# CH32FVx0xR-NFC-EVT-R0-1v2.net
KiCad netlist of a schematic drawn in Altium Designer
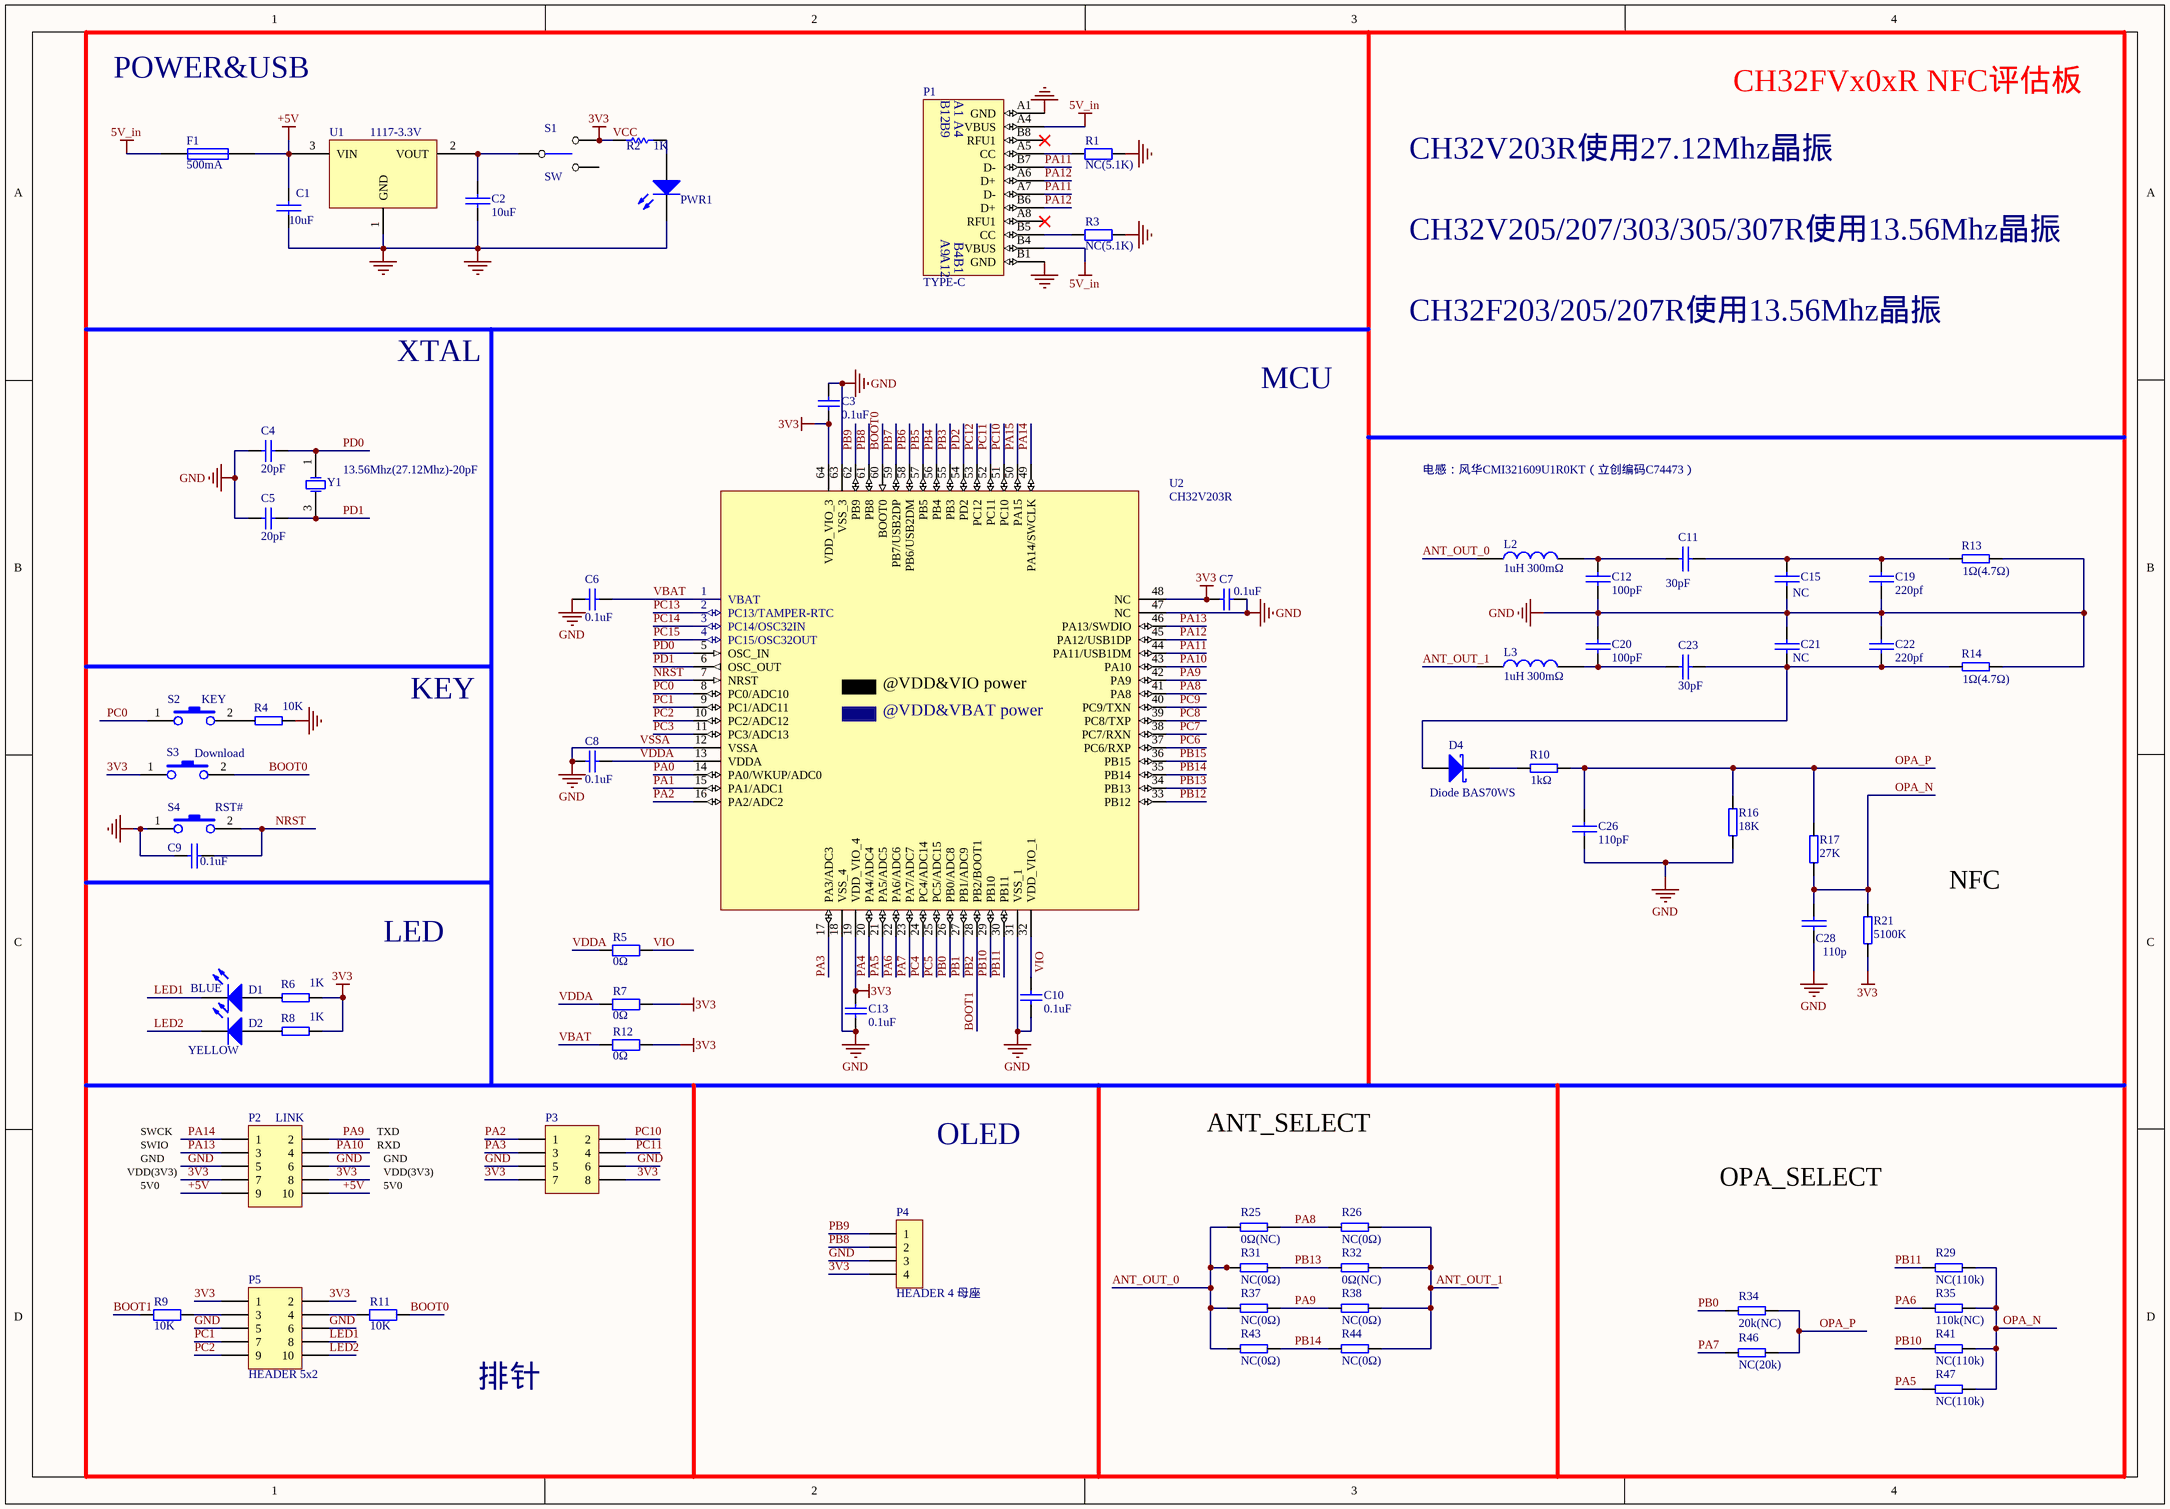
[diagram p0: CH32FVx0xR-NFC-EVT-R0-1v2.SchDoc]

(export (version "E")
  (design (tool "Eeschema 10.0.6"))
  (components
    (comp (ref "C1")
      (value "10uF")
      (footprint "3216_C")
      (description "Capacitor")
      (libsource (lib "") (part "CAP_1"))
    )
    (comp (ref "C2")
      (value "10uF")
      (footprint "3216_C")
      (description "Capacitor")
      (libsource (lib "") (part "CAP_1"))
    )
    (comp (ref "C3")
      (value "0.1uF")
      (footprint "0603_C")
      (description "Capacitor")
      (libsource (lib "Miscellaneous Devices") (part "Cap"))
    )
    (comp (ref "C4")
      (value "20pF")
      (footprint "0603_C")
      (description "Capacitor")
      (libsource (lib "Miscellaneous Devices") (part "Cap"))
    )
    (comp (ref "C5")
      (value "20pF")
      (footprint "0603_C")
      (description "Capacitor")
      (libsource (lib "Miscellaneous Devices") (part "Cap"))
    )
    (comp (ref "C6")
      (value "0.1uF")
      (footprint "0603_C")
      (description "Capacitor")
      (libsource (lib "Miscellaneous Devices") (part "Cap"))
    )
    (comp (ref "C7")
      (value "0.1uF")
      (footprint "0603_C")
      (description "Capacitor")
      (libsource (lib "Miscellaneous Devices") (part "Cap"))
    )
    (comp (ref "C8")
      (value "0.1uF")
      (footprint "0603_C")
      (description "Capacitor")
      (libsource (lib "Miscellaneous Devices") (part "Cap"))
    )
    (comp (ref "C9")
      (value "0.1uF")
      (footprint "0603_C")
      (description "Capacitor")
      (libsource (lib "*") (part "CAP"))
    )
    (comp (ref "C10")
      (value "0.1uF")
      (footprint "0603_C")
      (description "Capacitor")
      (libsource (lib "Miscellaneous Devices") (part "Cap"))
    )
    (comp (ref "C11")
      (value "30pF")
      (footprint "0603_C")
      (description "Capacitor")
      (libsource (lib "wch_sch_others") (part "CAP"))
    )
    (comp (ref "C12")
      (value "100pF")
      (footprint "0603_C")
      (description "Capacitor")
      (libsource (lib "wch_sch_others") (part "CAP"))
    )
    (comp (ref "C13")
      (value "0.1uF")
      (footprint "0603_C")
      (description "Capacitor")
      (libsource (lib "Miscellaneous Devices") (part "Cap"))
    )
    (comp (ref "C15")
      (value "NC")
      (footprint "0603_C")
      (description "Capacitor")
      (libsource (lib "wch_sch_others") (part "CAP"))
    )
    (comp (ref "C19")
      (value "220pf")
      (footprint "0603_C")
      (description "Capacitor")
      (libsource (lib "wch_sch_others") (part "CAP"))
    )
    (comp (ref "C20")
      (value "100pF")
      (footprint "0603_C")
      (description "Capacitor")
      (libsource (lib "wch_sch_others") (part "CAP"))
    )
    (comp (ref "C21")
      (value "NC")
      (footprint "0603_C")
      (description "Capacitor")
      (libsource (lib "wch_sch_others") (part "CAP"))
    )
    (comp (ref "C22")
      (value "220pf")
      (footprint "0603_C")
      (description "Capacitor")
      (libsource (lib "wch_sch_others") (part "CAP"))
    )
    (comp (ref "C23")
      (value "30pF")
      (footprint "0603_C")
      (description "Capacitor")
      (libsource (lib "wch_sch_others") (part "CAP"))
    )
    (comp (ref "C26")
      (value "110pF")
      (footprint "0603_C")
      (description "Capacitor")
      (libsource (lib "wch_sch_others") (part "CAP"))
    )
    (comp (ref "C28")
      (value "110p")
      (footprint "0603_C")
      (description "Capacitor")
      (libsource (lib "wch_sch_others") (part "CAP"))
    )
    (comp (ref "D1")
      (value "BLUE")
      (footprint "0603+")
      (description "Typical INFRARED GaAs LED")
      (fields (field (name "PUBLISHER") "Altium Limited"))
      (libsource (lib "*") (part "LED0"))
    )
    (comp (ref "D2")
      (value "YELLOW")
      (footprint "0603+")
      (description "Typical INFRARED GaAs LED")
      (fields (field (name "PUBLISHER") "Altium Limited"))
      (libsource (lib "*") (part "LED0"))
    )
    (comp (ref "D4")
      (value "Diode BAS70WS")
      (footprint "3528+")
      (description "Silicon AF Schottky Diode for High-Speed Switching")
      (fields (field (name "PUBLISHER") "Altium Limited"))
      (libsource (lib "Miscellaneous Devices") (part "Diode BAS70"))
    )
    (comp (ref "F1")
      (value "500mA")
      (footprint "0805")
      (description "Fuse")
      (libsource (lib "*") (part "FUSE1"))
    )
    (comp (ref "L2") (value "1uH 300mΩ") (footprint "0805") (libsource (lib "*") (part "INDUCTOR")))
    (comp (ref "L3") (value "1uH 300mΩ") (footprint "0805") (libsource (lib "*") (part "INDUCTOR")))
    (comp (ref "P1")
      (value "TYPE-C")
      (footprint "TYPE-C-Receptacle-2.0")
      (libsource (lib "*") (part "TYPE-C1"))
    )
    (comp (ref "P2")
      (value "LINK")
      (footprint "IDC10-2.54mm")
      (description "Header, 5-Pin, Dual row, Right Angle")
      (fields (field (name "PUBLISHER") "Altium Limited"))
      (libsource (lib "Miscellaneous Connectors") (part "Header 5X2H"))
    )
    (comp (ref "P3")
      (value "Header 4X2")
      (footprint "IDC8-2.54mm")
      (description "Header, 4-Pin, Dual row")
      (fields (field (name "PUBLISHER") "Altium Limited"))
      (libsource (lib "Miscellaneous Connectors") (part "Header 4X2"))
    )
    (comp (ref "P4")
      (value "HEADER 4 母座")
      (footprint "SIP4-2.54mm")
      (description "Header, 4-Pin")
      (libsource (lib "wch_sch_others") (part "HEADER 4"))
    )
    (comp (ref "P5")
      (value "HEADER 5x2")
      (footprint "MYPCB:IDC10-2.54mm")
      (description "Header, 5-Pin, Dual row")
      (libsource (lib "wch_sch_others") (part "HEADER 5x2"))
    )
    (comp (ref "PWR1")
      (value "POWER  red")
      (footprint "0603+")
      (description "Typical INFRARED GaAs LED")
      (fields (field (name "PUBLISHER") "Altium Limited"))
      (libsource (lib "Miscellaneous Devices") (part "LED0"))
    )
    (comp (ref "R1")
      (value "NC(5.1K)")
      (footprint "0603")
      (description "Resistor")
      (libsource (lib "") (part "Res2_1"))
    )
    (comp (ref "R2")
      (value "1K")
      (footprint "0603")
      (description "Semiconductor Resistor")
      (libsource (lib "Miscellaneous Devices") (part "Res Semi"))
    )
    (comp (ref "R3")
      (value "NC(5.1K)")
      (footprint "0603")
      (description "Resistor")
      (libsource (lib "") (part "Res2_1"))
    )
    (comp (ref "R4") (value "10K") (footprint "0603") (libsource (lib "wch_sch_others") (part "RES")))
    (comp (ref "R5")
      (value "0Ω")
      (footprint "0603")
      (description "Resistor")
      (libsource (lib "Miscellaneous Devices") (part "Res2"))
    )
    (comp (ref "R6") (value "1K") (footprint "0603") (libsource (lib "wch_sch_others") (part "RES")))
    (comp (ref "R7")
      (value "0Ω")
      (footprint "0603")
      (description "Resistor")
      (libsource (lib "Miscellaneous Devices") (part "Res2"))
    )
    (comp (ref "R8") (value "1K") (footprint "0603") (libsource (lib "wch_sch_others") (part "RES")))
    (comp (ref "R9")
      (value "10K")
      (footprint "0603")
      (description "Resistor")
      (libsource (lib "") (part "Res2_1"))
    )
    (comp (ref "R10") (value "1kΩ") (footprint "0603") (libsource (lib "wch_sch_others") (part "RES")))
    (comp (ref "R11")
      (value "10K")
      (footprint "0603")
      (description "Resistor")
      (libsource (lib "") (part "Res2_1"))
    )
    (comp (ref "R12")
      (value "0Ω")
      (footprint "0603")
      (description "Resistor")
      (libsource (lib "Miscellaneous Devices") (part "Res2"))
    )
    (comp (ref "R13") (value "1Ω(4.7Ω)") (footprint "0603") (libsource (lib "wch_sch_others") (part "RES")))
    (comp (ref "R14") (value "1Ω(4.7Ω)") (footprint "0603") (libsource (lib "wch_sch_others") (part "RES")))
    (comp (ref "R16") (value "18K") (footprint "0603") (libsource (lib "wch_sch_others") (part "RES")))
    (comp (ref "R17") (value "27K") (footprint "0603") (libsource (lib "wch_sch_others") (part "RES")))
    (comp (ref "R21") (value "5100K") (footprint "0603") (libsource (lib "wch_sch_others") (part "RES")))
    (comp (ref "R25") (value "0Ω(NC)") (footprint "0603") (libsource (lib "wch_sch_others") (part "RES")))
    (comp (ref "R26") (value "NC(0Ω)") (footprint "0603") (libsource (lib "wch_sch_others") (part "RES")))
    (comp (ref "R29") (value "NC(110k)") (footprint "0603") (libsource (lib "wch_sch_others") (part "RES")))
    (comp (ref "R31") (value "NC(0Ω)") (footprint "0603") (libsource (lib "wch_sch_others") (part "RES")))
    (comp (ref "R32") (value "0Ω(NC)") (footprint "0603") (libsource (lib "wch_sch_others") (part "RES")))
    (comp (ref "R34") (value "20k(NC)") (footprint "0603") (libsource (lib "wch_sch_others") (part "RES")))
    (comp (ref "R35") (value "110k(NC)") (footprint "0603") (libsource (lib "wch_sch_others") (part "RES")))
    (comp (ref "R37") (value "NC(0Ω)") (footprint "0603") (libsource (lib "wch_sch_others") (part "RES")))
    (comp (ref "R38") (value "NC(0Ω)") (footprint "0603") (libsource (lib "wch_sch_others") (part "RES")))
    (comp (ref "R41") (value "NC(110k)") (footprint "0603") (libsource (lib "wch_sch_others") (part "RES")))
    (comp (ref "R43") (value "NC(0Ω)") (footprint "0603") (libsource (lib "wch_sch_others") (part "RES")))
    (comp (ref "R44") (value "NC(0Ω)") (footprint "0603") (libsource (lib "wch_sch_others") (part "RES")))
    (comp (ref "R46") (value "NC(20k)") (footprint "0603") (libsource (lib "wch_sch_others") (part "RES")))
    (comp (ref "R47") (value "NC(110k)") (footprint "0603") (libsource (lib "wch_sch_others") (part "RES")))
    (comp (ref "S1") (value "SW") (footprint "SW1") (libsource (lib "MYSCH") (part "SW")))
    (comp (ref "S2")
      (value "KEY")
      (footprint "SMD_6.1x3.65x2.5mm-KEY")
      (libsource (lib "wch_sch_others") (part "KEY1"))
    )
    (comp (ref "S3")
      (value "Download")
      (footprint "SMD_6.1x3.65x2.5mm-KEY")
      (libsource (lib "wch_sch_others") (part "KEY1"))
    )
    (comp (ref "S4")
      (value "RST#")
      (footprint "SMD_6.1x3.65x2.5mm-KEY")
      (libsource (lib "wch_sch_others") (part "KEY1"))
    )
    (comp (ref "U1")
      (value "1117-3.3V")
      (footprint "SOT-223")
      (libsource (lib "wch_sch_others") (part "1117-3.3V"))
    )
    (comp (ref "U2")
      (value "CH32V203R")
      (footprint "LQFP64M_10x10")
      (description "RISC-V HD-MCU, 10M Ethernet, 2*USB, CAN")
      (libsource (lib "CHXXX") (part "CH32V203R"))
    )
    (comp (ref "Y1")
      (value "13.56Mhz(27.12Mhz)-20pF")
      (footprint "XT3225")
      (description "Crystal Oscillator")
      (fields (field (name "PUBLISHER") "Altium Limited"))
      (libsource (lib "Miscellaneous Devices") (part "XTAL"))
    )
  )
  (nets
    (net (code "1") (name "+5V") (class "Default")
      (node (ref "C1") (pin "1") (pinfunction "1_1") (pintype "passive"))
      (node (ref "F1") (pin "2") (pinfunction "2_2") (pintype "passive"))
      (node (ref "P2") (pin "10") (pinfunction "10_10") (pintype "passive"))
      (node (ref "P2") (pin "9") (pinfunction "9_9") (pintype "passive"))
      (node (ref "U1") (pin "3") (pinfunction "VIN_3") (pintype "passive"))
    )
    (net (code "2") (name "/ANT_OUT_0") (class "Default")
      (node (ref "L2") (pin "1") (pinfunction "1_1") (pintype "passive"))
      (node (ref "R25") (pin "2") (pintype "passive"))
      (node (ref "R31") (pin "2") (pintype "passive"))
      (node (ref "R37") (pin "2") (pintype "passive"))
      (node (ref "R43") (pin "2") (pintype "passive"))
    )
    (net (code "3") (name "/ANT_OUT_1") (class "Default")
      (node (ref "L3") (pin "1") (pinfunction "1_1") (pintype "passive"))
      (node (ref "R26") (pin "1") (pintype "passive"))
      (node (ref "R32") (pin "1") (pintype "passive"))
      (node (ref "R38") (pin "1") (pintype "passive"))
      (node (ref "R44") (pin "1") (pintype "passive"))
    )
    (net (code "4") (name "/BOOT0") (class "Default")
      (node (ref "R11") (pin "2") (pinfunction "2_2") (pintype "passive"))
      (node (ref "S3") (pin "2") (pinfunction "2_2") (pintype "passive"))
      (node (ref "U2") (pin "60") (pinfunction "BOOT0_60") (pintype "input"))
    )
    (net (code "5") (name "/BOOT1") (class "Default")
      (node (ref "R9") (pin "1") (pinfunction "1_1") (pintype "passive"))
      (node (ref "U2") (pin "28") (pinfunction "PB2/BOOT1_28") (pintype "bidirectional"))
    )
    (net (code "6") (name "/LED1") (class "Default")
      (node (ref "D1") (pin "2") (pinfunction "K_2") (pintype "passive"))
      (node (ref "P5") (pin "8") (pinfunction "8_8") (pintype "passive"))
    )
    (net (code "7") (name "/LED2") (class "Default")
      (node (ref "D2") (pin "2") (pinfunction "K_2") (pintype "passive"))
      (node (ref "P5") (pin "10") (pinfunction "10_10") (pintype "passive"))
    )
    (net (code "8") (name "/NRST") (class "Default")
      (node (ref "C9") (pin "2") (pinfunction "2_2") (pintype "passive"))
      (node (ref "S4") (pin "2") (pinfunction "2_2") (pintype "passive"))
      (node (ref "U2") (pin "7") (pinfunction "NRST_7") (pintype "input"))
    )
    (net (code "9") (name "/OPA_N") (class "Default")
      (node (ref "C28") (pin "2") (pinfunction "2_2") (pintype "passive"))
      (node (ref "R17") (pin "1") (pintype "passive"))
      (node (ref "R21") (pin "2") (pintype "passive"))
      (node (ref "R29") (pin "1") (pintype "passive"))
      (node (ref "R35") (pin "1") (pintype "passive"))
      (node (ref "R41") (pin "1") (pintype "passive"))
      (node (ref "R47") (pin "1") (pintype "passive"))
    )
    (net (code "10") (name "/OPA_P") (class "Default")
      (node (ref "C26") (pin "2") (pinfunction "2_2") (pintype "passive"))
      (node (ref "R10") (pin "2") (pintype "passive"))
      (node (ref "R16") (pin "2") (pintype "passive"))
      (node (ref "R17") (pin "2") (pintype "passive"))
      (node (ref "R34") (pin "1") (pintype "passive"))
      (node (ref "R46") (pin "1") (pintype "passive"))
    )
    (net (code "11") (name "/PA0") (class "Default")
      (node (ref "U2") (pin "14") (pinfunction "PA0/WKUP/ADC0_14") (pintype "bidirectional"))
    )
    (net (code "12") (name "/PA1") (class "Default")
      (node (ref "U2") (pin "15") (pinfunction "PA1/ADC1_15") (pintype "bidirectional"))
    )
    (net (code "13") (name "/PA2") (class "Default")
      (node (ref "P3") (pin "1") (pinfunction "1_1") (pintype "passive"))
      (node (ref "U2") (pin "16") (pinfunction "PA2/ADC2_16") (pintype "bidirectional"))
    )
    (net (code "14") (name "/PA3") (class "Default")
      (node (ref "P3") (pin "3") (pinfunction "3_3") (pintype "passive"))
      (node (ref "U2") (pin "17") (pinfunction "PA3/ADC3_17") (pintype "bidirectional"))
    )
    (net (code "15") (name "/PA4") (class "Default")
      (node (ref "U2") (pin "20") (pinfunction "PA4/ADC4_20") (pintype "bidirectional"))
    )
    (net (code "16") (name "/PA5") (class "Default")
      (node (ref "R47") (pin "2") (pintype "passive"))
      (node (ref "U2") (pin "21") (pinfunction "PA5/ADC5_21") (pintype "bidirectional"))
    )
    (net (code "17") (name "/PA6") (class "Default")
      (node (ref "R35") (pin "2") (pintype "passive"))
      (node (ref "U2") (pin "22") (pinfunction "PA6/ADC6_22") (pintype "bidirectional"))
    )
    (net (code "18") (name "/PA7") (class "Default")
      (node (ref "R46") (pin "2") (pintype "passive"))
      (node (ref "U2") (pin "23") (pinfunction "PA7/ADC7_23") (pintype "bidirectional"))
    )
    (net (code "19") (name "/PA8") (class "Default")
      (node (ref "R25") (pin "1") (pintype "passive"))
      (node (ref "R26") (pin "2") (pintype "passive"))
      (node (ref "U2") (pin "41") (pinfunction "PA8_41") (pintype "bidirectional"))
    )
    (net (code "20") (name "/PA9") (class "Default")
      (node (ref "P2") (pin "2") (pinfunction "2_2") (pintype "passive"))
      (node (ref "R37") (pin "1") (pintype "passive"))
      (node (ref "R38") (pin "2") (pintype "passive"))
      (node (ref "U2") (pin "42") (pinfunction "PA9_42") (pintype "bidirectional"))
    )
    (net (code "21") (name "/PA10") (class "Default")
      (node (ref "P2") (pin "4") (pinfunction "4_4") (pintype "passive"))
      (node (ref "U2") (pin "43") (pinfunction "PA10_43") (pintype "bidirectional"))
    )
    (net (code "22") (name "/PA11") (class "Default")
      (node (ref "P1") (pin "A7") (pinfunction "D-_A7") (pintype "bidirectional"))
      (node (ref "P1") (pin "B7") (pinfunction "D-_B7") (pintype "bidirectional"))
      (node (ref "U2") (pin "44") (pinfunction "PA11/USB1DM_44") (pintype "bidirectional"))
    )
    (net (code "23") (name "/PA12") (class "Default")
      (node (ref "P1") (pin "A6") (pinfunction "D+_A6") (pintype "bidirectional"))
      (node (ref "P1") (pin "B6") (pinfunction "D+_B6") (pintype "bidirectional"))
      (node (ref "U2") (pin "45") (pinfunction "PA12/USB1DP_45") (pintype "bidirectional"))
    )
    (net (code "24") (name "/PA13") (class "Default")
      (node (ref "P2") (pin "3") (pinfunction "3_3") (pintype "passive"))
      (node (ref "U2") (pin "46") (pinfunction "PA13/SWDIO_46") (pintype "bidirectional"))
    )
    (net (code "25") (name "/PA14") (class "Default")
      (node (ref "P2") (pin "1") (pinfunction "1_1") (pintype "passive"))
      (node (ref "U2") (pin "49") (pinfunction "PA14/SWCLK_49") (pintype "bidirectional"))
    )
    (net (code "26") (name "/PA15") (class "Default")
      (node (ref "U2") (pin "50") (pinfunction "PA15_50") (pintype "bidirectional"))
    )
    (net (code "27") (name "/PB0") (class "Default")
      (node (ref "R34") (pin "2") (pintype "passive"))
      (node (ref "U2") (pin "26") (pinfunction "PB0/ADC8_26") (pintype "bidirectional"))
    )
    (net (code "28") (name "/PB1") (class "Default")
      (node (ref "U2") (pin "27") (pinfunction "PB1/ADC9_27") (pintype "bidirectional"))
    )
    (net (code "29") (name "/PB3") (class "Default")
      (node (ref "U2") (pin "55") (pinfunction "PB3_55") (pintype "bidirectional"))
    )
    (net (code "30") (name "/PB4") (class "Default")
      (node (ref "U2") (pin "56") (pinfunction "PB4_56") (pintype "bidirectional"))
    )
    (net (code "31") (name "/PB5") (class "Default")
      (node (ref "U2") (pin "57") (pinfunction "PB5_57") (pintype "bidirectional"))
    )
    (net (code "32") (name "/PB6") (class "Default")
      (node (ref "U2") (pin "58") (pinfunction "PB6/USB2DM_58") (pintype "bidirectional"))
    )
    (net (code "33") (name "/PB7") (class "Default")
      (node (ref "U2") (pin "59") (pinfunction "PB7/USB2DP_59") (pintype "bidirectional"))
    )
    (net (code "34") (name "/PB8") (class "Default")
      (node (ref "P4") (pin "2") (pinfunction "2_2") (pintype "passive"))
      (node (ref "U2") (pin "61") (pinfunction "PB8_61") (pintype "bidirectional"))
    )
    (net (code "35") (name "/PB9") (class "Default")
      (node (ref "P4") (pin "1") (pinfunction "1_1") (pintype "passive"))
      (node (ref "U2") (pin "62") (pinfunction "PB9_62") (pintype "bidirectional"))
    )
    (net (code "36") (name "/PB10") (class "Default")
      (node (ref "R41") (pin "2") (pintype "passive"))
      (node (ref "U2") (pin "29") (pinfunction "PB10_29") (pintype "bidirectional"))
    )
    (net (code "37") (name "/PB11") (class "Default")
      (node (ref "R29") (pin "2") (pintype "passive"))
      (node (ref "U2") (pin "30") (pinfunction "PB11_30") (pintype "bidirectional"))
    )
    (net (code "38") (name "/PB12") (class "Default")
      (node (ref "U2") (pin "33") (pinfunction "PB12_33") (pintype "bidirectional"))
    )
    (net (code "39") (name "/PB13") (class "Default")
      (node (ref "R31") (pin "1") (pintype "passive"))
      (node (ref "R32") (pin "2") (pintype "passive"))
      (node (ref "U2") (pin "34") (pinfunction "PB13_34") (pintype "bidirectional"))
    )
    (net (code "40") (name "/PB14") (class "Default")
      (node (ref "R43") (pin "1") (pintype "passive"))
      (node (ref "R44") (pin "2") (pintype "passive"))
      (node (ref "U2") (pin "35") (pinfunction "PB14_35") (pintype "bidirectional"))
    )
    (net (code "41") (name "/PB15") (class "Default")
      (node (ref "U2") (pin "36") (pinfunction "PB15_36") (pintype "bidirectional"))
    )
    (net (code "42") (name "/PC0") (class "Default")
      (node (ref "S2") (pin "1") (pinfunction "1_1") (pintype "passive"))
      (node (ref "U2") (pin "8") (pinfunction "PC0/ADC10_8") (pintype "bidirectional"))
    )
    (net (code "43") (name "/PC1") (class "Default")
      (node (ref "P5") (pin "7") (pinfunction "7_7") (pintype "passive"))
      (node (ref "U2") (pin "9") (pinfunction "PC1/ADC11_9") (pintype "bidirectional"))
    )
    (net (code "44") (name "/PC2") (class "Default")
      (node (ref "P5") (pin "9") (pinfunction "9_9") (pintype "passive"))
      (node (ref "U2") (pin "10") (pinfunction "PC2/ADC12_10") (pintype "bidirectional"))
    )
    (net (code "45") (name "/PC3") (class "Default")
      (node (ref "U2") (pin "11") (pinfunction "PC3/ADC13_11") (pintype "bidirectional"))
    )
    (net (code "46") (name "/PC4") (class "Default")
      (node (ref "U2") (pin "24") (pinfunction "PC4/ADC14_24") (pintype "bidirectional"))
    )
    (net (code "47") (name "/PC5") (class "Default")
      (node (ref "U2") (pin "25") (pinfunction "PC5/ADC15_25") (pintype "bidirectional"))
    )
    (net (code "48") (name "/PC6") (class "Default")
      (node (ref "U2") (pin "37") (pinfunction "PC6/RXP_37") (pintype "bidirectional"))
    )
    (net (code "49") (name "/PC7") (class "Default")
      (node (ref "U2") (pin "38") (pinfunction "PC7/RXN_38") (pintype "bidirectional"))
    )
    (net (code "50") (name "/PC8") (class "Default")
      (node (ref "U2") (pin "39") (pinfunction "PC8/TXP_39") (pintype "bidirectional"))
    )
    (net (code "51") (name "/PC9") (class "Default")
      (node (ref "U2") (pin "40") (pinfunction "PC9/TXN_40") (pintype "bidirectional"))
    )
    (net (code "52") (name "/PC10") (class "Default")
      (node (ref "P3") (pin "2") (pinfunction "2_2") (pintype "passive"))
      (node (ref "U2") (pin "51") (pinfunction "PC10_51") (pintype "bidirectional"))
    )
    (net (code "53") (name "/PC11") (class "Default")
      (node (ref "P3") (pin "4") (pinfunction "4_4") (pintype "passive"))
      (node (ref "U2") (pin "52") (pinfunction "PC11_52") (pintype "bidirectional"))
    )
    (net (code "54") (name "/PC12") (class "Default")
      (node (ref "U2") (pin "53") (pinfunction "PC12_53") (pintype "bidirectional"))
    )
    (net (code "55") (name "/PC13") (class "Default")
      (node (ref "U2") (pin "2") (pinfunction "PC13/TAMPER-RTC_2") (pintype "bidirectional"))
    )
    (net (code "56") (name "/PC14") (class "Default")
      (node (ref "U2") (pin "3") (pinfunction "PC14/OSC32IN_3") (pintype "bidirectional"))
    )
    (net (code "57") (name "/PC15") (class "Default")
      (node (ref "U2") (pin "4") (pinfunction "PC15/OSC32OUT_4") (pintype "bidirectional"))
    )
    (net (code "58") (name "/PD0") (class "Default")
      (node (ref "C4") (pin "2") (pinfunction "2_2") (pintype "passive"))
      (node (ref "U2") (pin "5") (pinfunction "OSC_IN_5") (pintype "input"))
      (node (ref "Y1") (pin "1") (pinfunction "OSC1_1") (pintype "passive"))
    )
    (net (code "59") (name "/PD1") (class "Default")
      (node (ref "C5") (pin "2") (pinfunction "2_2") (pintype "passive"))
      (node (ref "U2") (pin "6") (pinfunction "OSC_OUT_6") (pintype "output"))
      (node (ref "Y1") (pin "3") (pinfunction "OSC2_3") (pintype "passive"))
    )
    (net (code "60") (name "/PD2") (class "Default")
      (node (ref "U2") (pin "54") (pinfunction "PD2_54") (pintype "bidirectional"))
    )
    (net (code "61") (name "/VBAT") (class "Default")
      (node (ref "C6") (pin "1") (pinfunction "1_1") (pintype "passive"))
      (node (ref "R12") (pin "2") (pinfunction "2_2") (pintype "passive"))
      (node (ref "U2") (pin "1") (pinfunction "VBAT_1") (pintype "power_in"))
    )
    (net (code "62") (name "/VDDA") (class "Default")
      (node (ref "C8") (pin "1") (pinfunction "1_1") (pintype "passive"))
      (node (ref "R5") (pin "2") (pinfunction "2_2") (pintype "passive"))
      (node (ref "R7") (pin "2") (pinfunction "2_2") (pintype "passive"))
      (node (ref "U2") (pin "13") (pinfunction "VDDA_13") (pintype "power_in"))
    )
    (net (code "63") (name "/VIO") (class "Default")
      (node (ref "C10") (pin "2") (pinfunction "2_2") (pintype "passive"))
      (node (ref "R5") (pin "1") (pinfunction "1_1") (pintype "passive"))
      (node (ref "U2") (pin "32") (pinfunction "VDD_VIO_1_32") (pintype "power_in"))
    )
    (net (code "64") (name "3V3") (class "Default")
      (node (ref "C13") (pin "2") (pinfunction "2_2") (pintype "passive"))
      (node (ref "C3") (pin "2") (pinfunction "2_2") (pintype "passive"))
      (node (ref "C7") (pin "2") (pinfunction "2_2") (pintype "passive"))
      (node (ref "P2") (pin "7") (pinfunction "7_7") (pintype "passive"))
      (node (ref "P2") (pin "8") (pinfunction "8_8") (pintype "passive"))
      (node (ref "P3") (pin "7") (pinfunction "7_7") (pintype "passive"))
      (node (ref "P3") (pin "8") (pinfunction "8_8") (pintype "passive"))
      (node (ref "P4") (pin "4") (pinfunction "4_4") (pintype "passive"))
      (node (ref "P5") (pin "1") (pinfunction "1_1") (pintype "passive"))
      (node (ref "P5") (pin "2") (pinfunction "2_2") (pintype "passive"))
      (node (ref "R12") (pin "1") (pinfunction "1_1") (pintype "passive"))
      (node (ref "R2") (pin "2") (pinfunction "2_2") (pintype "passive"))
      (node (ref "R21") (pin "1") (pintype "passive"))
      (node (ref "R6") (pin "1") (pintype "passive"))
      (node (ref "R7") (pin "1") (pinfunction "1_1") (pintype "passive"))
      (node (ref "R8") (pin "1") (pintype "passive"))
      (node (ref "S1") (pin "3") (pinfunction "3_3") (pintype "passive"))
      (node (ref "S3") (pin "1") (pinfunction "1_1") (pintype "passive"))
      (node (ref "U2") (pin "19") (pinfunction "VDD_VIO_4_19") (pintype "power_in"))
      (node (ref "U2") (pin "48") (pinfunction "NC_48") (pintype "power_in"))
      (node (ref "U2") (pin "64") (pinfunction "VDD_VIO_3_64") (pintype "power_in"))
    )
    (net (code "65") (name "5V_in") (class "Default")
      (node (ref "F1") (pin "1") (pinfunction "1_1") (pintype "passive"))
      (node (ref "P1") (pin "A4") (pinfunction "VBUS_A4") (pintype "bidirectional"))
      (node (ref "P1") (pin "B4") (pinfunction "VBUS_B4") (pintype "bidirectional"))
    )
    (net (code "66") (name "GND") (class "Default")
      (node (ref "C1") (pin "2") (pinfunction "2_2") (pintype "passive"))
      (node (ref "C10") (pin "1") (pinfunction "1_1") (pintype "passive"))
      (node (ref "C12") (pin "1") (pinfunction "1_1") (pintype "passive"))
      (node (ref "C13") (pin "1") (pinfunction "1_1") (pintype "passive"))
      (node (ref "C15") (pin "1") (pinfunction "1_1") (pintype "passive"))
      (node (ref "C19") (pin "1") (pinfunction "1_1") (pintype "passive"))
      (node (ref "C2") (pin "2") (pinfunction "2_2") (pintype "passive"))
      (node (ref "C20") (pin "2") (pinfunction "2_2") (pintype "passive"))
      (node (ref "C21") (pin "2") (pinfunction "2_2") (pintype "passive"))
      (node (ref "C22") (pin "2") (pinfunction "2_2") (pintype "passive"))
      (node (ref "C26") (pin "1") (pinfunction "1_1") (pintype "passive"))
      (node (ref "C28") (pin "1") (pinfunction "1_1") (pintype "passive"))
      (node (ref "C3") (pin "1") (pinfunction "1_1") (pintype "passive"))
      (node (ref "C4") (pin "1") (pinfunction "1_1") (pintype "passive"))
      (node (ref "C5") (pin "1") (pinfunction "1_1") (pintype "passive"))
      (node (ref "C6") (pin "2") (pinfunction "2_2") (pintype "passive"))
      (node (ref "C7") (pin "1") (pinfunction "1_1") (pintype "passive"))
      (node (ref "C8") (pin "2") (pinfunction "2_2") (pintype "passive"))
      (node (ref "C9") (pin "1") (pinfunction "1_1") (pintype "passive"))
      (node (ref "P1") (pin "A1") (pinfunction "GND_A1") (pintype "bidirectional"))
      (node (ref "P1") (pin "B1") (pinfunction "GND_B1") (pintype "bidirectional"))
      (node (ref "P2") (pin "5") (pinfunction "5_5") (pintype "passive"))
      (node (ref "P2") (pin "6") (pinfunction "6_6") (pintype "passive"))
      (node (ref "P3") (pin "5") (pinfunction "5_5") (pintype "passive"))
      (node (ref "P3") (pin "6") (pinfunction "6_6") (pintype "passive"))
      (node (ref "P4") (pin "3") (pinfunction "3_3") (pintype "passive"))
      (node (ref "P5") (pin "5") (pinfunction "5_5") (pintype "passive"))
      (node (ref "P5") (pin "6") (pinfunction "6_6") (pintype "passive"))
      (node (ref "PWR1") (pin "2") (pinfunction "K_2") (pintype "passive"))
      (node (ref "R1") (pin "2") (pinfunction "2_2") (pintype "passive"))
      (node (ref "R13") (pin "2") (pintype "passive"))
      (node (ref "R14") (pin "2") (pintype "passive"))
      (node (ref "R16") (pin "1") (pintype "passive"))
      (node (ref "R3") (pin "2") (pinfunction "2_2") (pintype "passive"))
      (node (ref "R4") (pin "1") (pintype "passive"))
      (node (ref "S4") (pin "1") (pinfunction "1_1") (pintype "passive"))
      (node (ref "U1") (pin "1") (pinfunction "GND_1") (pintype "passive"))
      (node (ref "U2") (pin "12") (pinfunction "VSSA_12") (pintype "power_in"))
      (node (ref "U2") (pin "18") (pinfunction "VSS_4_18") (pintype "power_in"))
      (node (ref "U2") (pin "31") (pinfunction "VSS_1_31") (pintype "power_in"))
      (node (ref "U2") (pin "47") (pinfunction "NC_47") (pintype "power_in"))
      (node (ref "U2") (pin "63") (pinfunction "VSS_3_63") (pintype "power_in"))
    )
    (net (code "67") (name "Net-(C11-Pad1)") (class "Default")
      (node (ref "C11") (pin "1") (pinfunction "1_1") (pintype "passive"))
      (node (ref "C12") (pin "2") (pinfunction "2_2") (pintype "passive"))
      (node (ref "L2") (pin "2") (pinfunction "2_2") (pintype "passive"))
    )
    (net (code "68") (name "Net-(C11-Pad2)") (class "Default")
      (node (ref "C11") (pin "2") (pinfunction "2_2") (pintype "passive"))
      (node (ref "C15") (pin "2") (pinfunction "2_2") (pintype "passive"))
      (node (ref "C19") (pin "2") (pinfunction "2_2") (pintype "passive"))
      (node (ref "R13") (pin "1") (pintype "passive"))
    )
    (net (code "69") (name "Net-(C20-Pad1)") (class "Default")
      (node (ref "C20") (pin "1") (pinfunction "1_1") (pintype "passive"))
      (node (ref "C23") (pin "1") (pinfunction "1_1") (pintype "passive"))
      (node (ref "L3") (pin "2") (pinfunction "2_2") (pintype "passive"))
    )
    (net (code "70") (name "Net-(D1-A)") (class "Default")
      (node (ref "D1") (pin "1") (pinfunction "A_1") (pintype "passive"))
      (node (ref "R6") (pin "2") (pintype "passive"))
    )
    (net (code "71") (name "Net-(D2-A)") (class "Default")
      (node (ref "D2") (pin "1") (pinfunction "A_1") (pintype "passive"))
      (node (ref "R8") (pin "2") (pintype "passive"))
    )
    (net (code "72") (name "Net-(D4-A)") (class "Default")
      (node (ref "C21") (pin "1") (pinfunction "1_1") (pintype "passive"))
      (node (ref "C22") (pin "1") (pinfunction "1_1") (pintype "passive"))
      (node (ref "C23") (pin "2") (pinfunction "2_2") (pintype "passive"))
      (node (ref "D4") (pin "1") (pinfunction "A_1") (pintype "passive"))
      (node (ref "R14") (pin "1") (pintype "passive"))
    )
    (net (code "73") (name "Net-(D4-K)") (class "Default")
      (node (ref "D4") (pin "2") (pinfunction "K_2") (pintype "passive"))
      (node (ref "R10") (pin "1") (pintype "passive"))
    )
    (net (code "74") (name "Net-(P1-CC-PadA5)") (class "Default")
      (node (ref "P1") (pin "A5") (pinfunction "CC_A5") (pintype "bidirectional"))
      (node (ref "R1") (pin "1") (pinfunction "1_1") (pintype "passive"))
    )
    (net (code "75") (name "Net-(P1-CC-PadB5)") (class "Default")
      (node (ref "P1") (pin "B5") (pinfunction "CC_B5") (pintype "bidirectional"))
      (node (ref "R3") (pin "1") (pinfunction "1_1") (pintype "passive"))
    )
    (net (code "76") (name "Net-(P5-Pad3)") (class "Default")
      (node (ref "P5") (pin "3") (pinfunction "3_3") (pintype "passive"))
      (node (ref "R9") (pin "2") (pinfunction "2_2") (pintype "passive"))
    )
    (net (code "77") (name "Net-(P5-Pad4)") (class "Default")
      (node (ref "P5") (pin "4") (pinfunction "4_4") (pintype "passive"))
      (node (ref "R11") (pin "1") (pinfunction "1_1") (pintype "passive"))
    )
    (net (code "78") (name "Net-(PWR1-A)") (class "Default")
      (node (ref "PWR1") (pin "1") (pinfunction "A_1") (pintype "passive"))
      (node (ref "R2") (pin "1") (pinfunction "1_1") (pintype "passive"))
    )
    (net (code "79") (name "Net-(R4-Pad2)") (class "Default")
      (node (ref "R4") (pin "2") (pintype "passive"))
      (node (ref "S2") (pin "2") (pinfunction "2_2") (pintype "passive"))
    )
    (net (code "80") (name "Net-(U1-VOUT)") (class "Default")
      (node (ref "C2") (pin "1") (pinfunction "1_1") (pintype "passive"))
      (node (ref "S1") (pin "1") (pinfunction "1_1") (pintype "passive"))
      (node (ref "U1") (pin "2") (pinfunction "VOUT_2") (pintype "passive"))
    )
    (net (code "81") (name "unconnected-(P1-RFU1-PadA8)") (class "Default")
      (node (ref "P1") (pin "A8") (pinfunction "RFU1_A8") (pintype "bidirectional+no_connect"))
    )
    (net (code "82") (name "unconnected-(P1-RFU1-PadB8)") (class "Default")
      (node (ref "P1") (pin "B8") (pinfunction "RFU1_B8") (pintype "bidirectional+no_connect"))
    )
    (net (code "83") (name "unconnected-(S1-Pad2)") (class "Default")
      (node (ref "S1") (pin "2") (pinfunction "2_2") (pintype "passive"))
    )
  )
)
